# main.net
KiCad netlist of a schematic drawn in Altium Designer
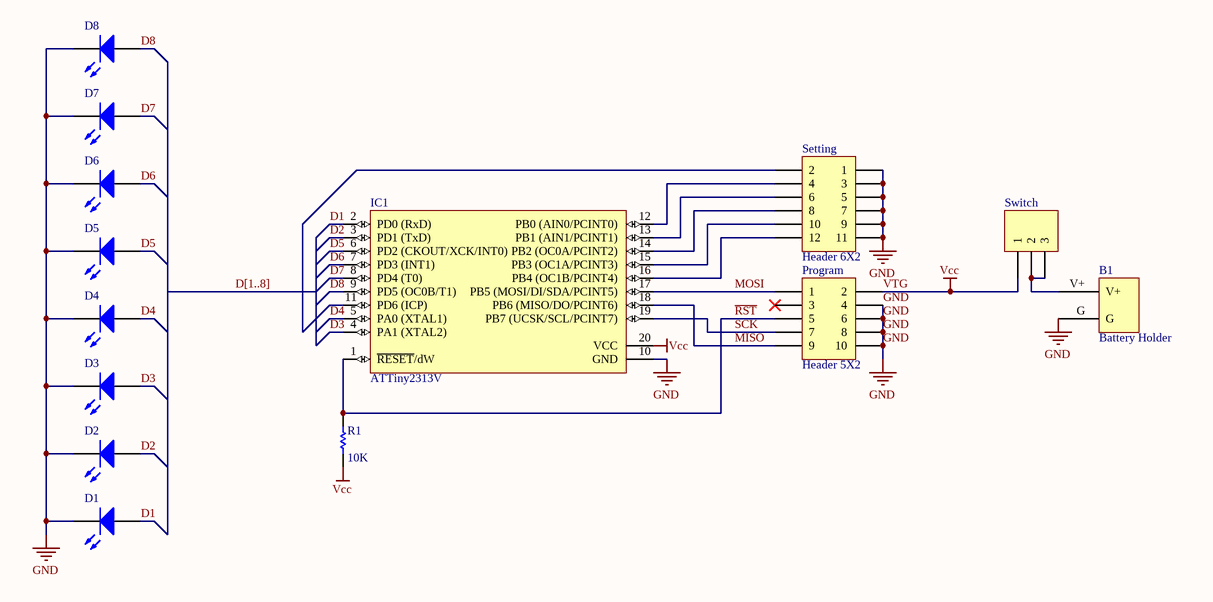
[diagram p0: main.SchDoc]

(export (version "E")
  (design (tool "Eeschema 10.0.6"))
  (components
    (comp (ref "B1")
      (value "Battery Holder")
      (footprint "Battery Holder")
      (libsource (lib "Connector") (part "Battery Holder"))
    )
    (comp (ref "D1")
      (value "LED1")
      (footprint "Led5mm")
      (description "Typical RED GaAs LED")
      (fields (field (name "PUBLISHER") "Altium Limited"))
      (libsource (lib "Miscellaneous Devices") (part "LED1"))
    )
    (comp (ref "D2")
      (value "LED1")
      (footprint "Led5mm")
      (description "Typical RED GaAs LED")
      (fields (field (name "PUBLISHER") "Altium Limited"))
      (libsource (lib "Miscellaneous Devices") (part "LED1"))
    )
    (comp (ref "D3")
      (value "LED1")
      (footprint "Led5mm")
      (description "Typical RED GaAs LED")
      (fields (field (name "PUBLISHER") "Altium Limited"))
      (libsource (lib "Miscellaneous Devices") (part "LED1"))
    )
    (comp (ref "D4")
      (value "LED1")
      (footprint "Led5mm")
      (description "Typical RED GaAs LED")
      (fields (field (name "PUBLISHER") "Altium Limited"))
      (libsource (lib "Miscellaneous Devices") (part "LED1"))
    )
    (comp (ref "D5")
      (value "LED1")
      (footprint "Led5mm")
      (description "Typical RED GaAs LED")
      (fields (field (name "PUBLISHER") "Altium Limited"))
      (libsource (lib "Miscellaneous Devices") (part "LED1"))
    )
    (comp (ref "D6")
      (value "LED1")
      (footprint "Led5mm")
      (description "Typical RED GaAs LED")
      (fields (field (name "PUBLISHER") "Altium Limited"))
      (libsource (lib "Miscellaneous Devices") (part "LED1"))
    )
    (comp (ref "D7")
      (value "LED1")
      (footprint "Led5mm")
      (description "Typical RED GaAs LED")
      (fields (field (name "PUBLISHER") "Altium Limited"))
      (libsource (lib "Miscellaneous Devices") (part "LED1"))
    )
    (comp (ref "D8")
      (value "LED1")
      (footprint "Led5mm")
      (description "Typical RED GaAs LED")
      (fields (field (name "PUBLISHER") "Altium Limited"))
      (libsource (lib "Miscellaneous Devices") (part "LED1"))
    )
    (comp (ref "IC1")
      (value "ATTiny2313V")
      (footprint "20P3")
      (description "8-Bit AVR Microcontroller with 2K Bytes of Flash Memory")
      (fields (field (name "PUBLISHER") "Altium Limited"))
      (libsource (lib "Atmel Microcontroller 8-Bit AVR") (part "ATtiny2313V-PI"))
    )
    (comp (ref "Program")
      (value "Header 5X2")
      (footprint "Box2x5")
      (description "Header, 5-Pin, Dual row")
      (fields (field (name "PUBLISHER") "Altium Limited"))
      (libsource (lib "Miscellaneous Connectors") (part "Header 5X2"))
    )
    (comp (ref "R1")
      (value "10K")
      (footprint "AXIAL-0.3")
      (description "Resistor")
      (fields (field (name "Comment") "Res1") (field (name "PUBLISHER") "Altium Limited"))
      (libsource (lib "Miscellaneous Devices") (part "Res1"))
    )
    (comp (ref "Setting")
      (value "Header 6X2")
      (footprint "DIP6SWITCH")
      (description "Header, 6-Pin, Dual row")
      (fields (field (name "PUBLISHER") "Altium Limited"))
      (libsource (lib "Miscellaneous Connectors") (part "Header 6X2"))
    )
    (comp (ref "Switch")
      (value "Header 3")
      (footprint "HDR1X3")
      (description "Header, 3-Pin")
      (fields (field (name "PUBLISHER") "Altium Limited"))
      (libsource (lib "Miscellaneous Connectors") (part "Header 3"))
    )
  )
  (nets
    (net (code "1") (name "/D1") (class "Default")
      (node (ref "D1") (pin "1") (pinfunction "A_1") (pintype "passive"))
      (node (ref "IC1") (pin "2") (pinfunction "PD0_(RxD)_2") (pintype "bidirectional"))
    )
    (net (code "2") (name "/D2") (class "Default")
      (node (ref "D2") (pin "1") (pinfunction "A_1") (pintype "passive"))
      (node (ref "IC1") (pin "3") (pinfunction "PD1_(TxD)_3") (pintype "bidirectional"))
    )
    (net (code "3") (name "/D3") (class "Default")
      (node (ref "D3") (pin "1") (pinfunction "A_1") (pintype "passive"))
      (node (ref "IC1") (pin "4") (pinfunction "PA1_(XTAL2)_4") (pintype "bidirectional"))
    )
    (net (code "4") (name "/D4") (class "Default")
      (node (ref "D4") (pin "1") (pinfunction "A_1") (pintype "passive"))
      (node (ref "IC1") (pin "5") (pinfunction "PA0_(XTAL1)_5") (pintype "bidirectional"))
    )
    (net (code "5") (name "/D5") (class "Default")
      (node (ref "D5") (pin "1") (pinfunction "A_1") (pintype "passive"))
      (node (ref "IC1") (pin "6") (pinfunction "PD2_(CKOUT/XCK/INT0)_6") (pintype "bidirectional"))
    )
    (net (code "6") (name "/D6") (class "Default")
      (node (ref "D6") (pin "1") (pinfunction "A_1") (pintype "passive"))
      (node (ref "IC1") (pin "7") (pinfunction "PD3_(INT1)_7") (pintype "bidirectional"))
    )
    (net (code "7") (name "/D7") (class "Default")
      (node (ref "D7") (pin "1") (pinfunction "A_1") (pintype "passive"))
      (node (ref "IC1") (pin "8") (pinfunction "PD4_(T0)_8") (pintype "bidirectional"))
    )
    (net (code "8") (name "/D8") (class "Default")
      (node (ref "D8") (pin "1") (pinfunction "A_1") (pintype "passive"))
      (node (ref "IC1") (pin "9") (pinfunction "PD5_(OC0B/T1)_9") (pintype "bidirectional"))
    )
    (net (code "10") (name "/MISO") (class "Default")
      (node (ref "IC1") (pin "18") (pinfunction "PB6_(MISO/DO/PCINT6)_18") (pintype "bidirectional"))
      (node (ref "Program") (pin "9") (pinfunction "9_9") (pintype "passive"))
    )
    (net (code "11") (name "/MOSI") (class "Default")
      (node (ref "IC1") (pin "17") (pinfunction "PB5_(MOSI/DI/SDA/PCINT5)_17") (pintype "bidirectional"))
      (node (ref "Program") (pin "1") (pinfunction "1_1") (pintype "passive"))
    )
    (net (code "12") (name "/SCK") (class "Default")
      (node (ref "IC1") (pin "19") (pinfunction "PB7_(UCSK/SCL/PCINT7)_19") (pintype "bidirectional"))
      (node (ref "Program") (pin "7") (pinfunction "7_7") (pintype "passive"))
    )
    (net (code "13") (name "/~{RST}") (class "Default")
      (node (ref "IC1") (pin "1") (pinfunction "~{RESET}/dW_1") (pintype "bidirectional"))
      (node (ref "Program") (pin "5") (pinfunction "5_5") (pintype "passive"))
      (node (ref "R1") (pin "2") (pinfunction "2_2") (pintype "passive"))
    )
    (net (code "14") (name "GND") (class "Default")
      (node (ref "B1") (pin "G") (pinfunction "G_G") (pintype "power_in"))
      (node (ref "D1") (pin "2") (pinfunction "K_2") (pintype "passive"))
      (node (ref "D2") (pin "2") (pinfunction "K_2") (pintype "passive"))
      (node (ref "D3") (pin "2") (pinfunction "K_2") (pintype "passive"))
      (node (ref "D4") (pin "2") (pinfunction "K_2") (pintype "passive"))
      (node (ref "D5") (pin "2") (pinfunction "K_2") (pintype "passive"))
      (node (ref "D6") (pin "2") (pinfunction "K_2") (pintype "passive"))
      (node (ref "D7") (pin "2") (pinfunction "K_2") (pintype "passive"))
      (node (ref "D8") (pin "2") (pinfunction "K_2") (pintype "passive"))
      (node (ref "IC1") (pin "10") (pinfunction "GND_10") (pintype "power_in"))
      (node (ref "Program") (pin "10") (pinfunction "10_10") (pintype "passive"))
      (node (ref "Program") (pin "4") (pinfunction "4_4") (pintype "passive"))
      (node (ref "Program") (pin "6") (pinfunction "6_6") (pintype "passive"))
      (node (ref "Program") (pin "8") (pinfunction "8_8") (pintype "passive"))
      (node (ref "Setting") (pin "1") (pinfunction "1_1") (pintype "passive"))
      (node (ref "Setting") (pin "11") (pinfunction "11_11") (pintype "passive"))
      (node (ref "Setting") (pin "3") (pinfunction "3_3") (pintype "passive"))
      (node (ref "Setting") (pin "5") (pinfunction "5_5") (pintype "passive"))
      (node (ref "Setting") (pin "7") (pinfunction "7_7") (pintype "passive"))
      (node (ref "Setting") (pin "9") (pinfunction "9_9") (pintype "passive"))
    )
    (net (code "15") (name "Net-(B1-PadV+)") (class "Default")
      (node (ref "B1") (pin "V+") (pinfunction "V+_V+") (pintype "power_in"))
      (node (ref "Switch") (pin "2") (pinfunction "2_2") (pintype "passive"))
      (node (ref "Switch") (pin "3") (pinfunction "3_3") (pintype "passive"))
    )
    (net (code "16") (name "Net-(IC1-PB0_(AIN0{slash}PCINT0))") (class "Default")
      (node (ref "IC1") (pin "12") (pinfunction "PB0_(AIN0/PCINT0)_12") (pintype "bidirectional"))
      (node (ref "Setting") (pin "4") (pinfunction "4_4") (pintype "passive"))
    )
    (net (code "17") (name "Net-(IC1-PB1_(AIN1{slash}PCINT1))") (class "Default")
      (node (ref "IC1") (pin "13") (pinfunction "PB1_(AIN1/PCINT1)_13") (pintype "bidirectional"))
      (node (ref "Setting") (pin "6") (pinfunction "6_6") (pintype "passive"))
    )
    (net (code "18") (name "Net-(IC1-PB2_(OC0A{slash}PCINT2))") (class "Default")
      (node (ref "IC1") (pin "14") (pinfunction "PB2_(OC0A/PCINT2)_14") (pintype "bidirectional"))
      (node (ref "Setting") (pin "8") (pinfunction "8_8") (pintype "passive"))
    )
    (net (code "19") (name "Net-(IC1-PB3_(OC1A{slash}PCINT3))") (class "Default")
      (node (ref "IC1") (pin "15") (pinfunction "PB3_(OC1A/PCINT3)_15") (pintype "bidirectional"))
      (node (ref "Setting") (pin "10") (pinfunction "10_10") (pintype "passive"))
    )
    (net (code "20") (name "Net-(IC1-PB4_(OC1B{slash}PCINT4))") (class "Default")
      (node (ref "IC1") (pin "16") (pinfunction "PB4_(OC1B/PCINT4)_16") (pintype "bidirectional"))
      (node (ref "Setting") (pin "12") (pinfunction "12_12") (pintype "passive"))
    )
    (net (code "21") (name "Net-(IC1-PD6_(ICP))") (class "Default")
      (node (ref "IC1") (pin "11") (pinfunction "PD6_(ICP)_11") (pintype "bidirectional"))
      (node (ref "Setting") (pin "2") (pinfunction "2_2") (pintype "passive"))
    )
    (net (code "22") (name "Vcc") (class "Default")
      (node (ref "IC1") (pin "20") (pinfunction "VCC_20") (pintype "power_in"))
      (node (ref "Program") (pin "2") (pinfunction "2_2") (pintype "passive"))
      (node (ref "R1") (pin "1") (pinfunction "1_1") (pintype "passive"))
      (node (ref "Switch") (pin "1") (pinfunction "1_1") (pintype "passive"))
    )
    (net (code "23") (name "unconnected-(Program-Pad3)") (class "Default")
      (node (ref "Program") (pin "3") (pinfunction "3_3") (pintype "passive+no_connect"))
    )
  )
)
